# DSO_Clock.net
KiCad netlist of a schematic drawn in Altium Designer
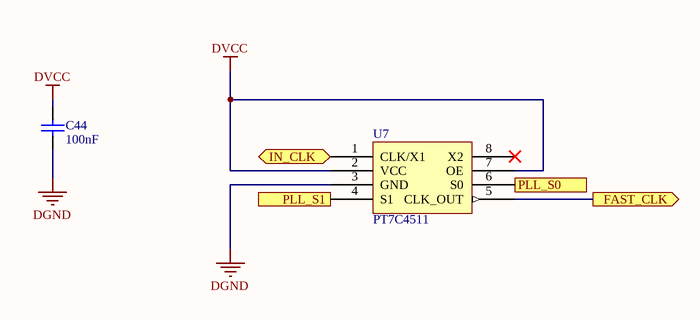
[diagram p0: DSO_Clock.SchDoc]

(export (version "E")
  (design (tool "Eeschema 10.0.6"))
  (components
    (comp (ref "C44")
      (value "100nF")
      (footprint "0805C")
      (description "Capacitor")
      (fields (field (name "REVIEWED BY") "RM - 2018/08/05"))
      (libsource (lib "DSO") (part "C"))
    )
    (comp (ref "U7")
      (value "PT7C4511")
      (footprint "SOIC-8")
      (description "PLL Clock Multiplier")
      (fields (field (name "REVIEWED BY") "RM - 2018/08/05"))
      (libsource (lib "DSO") (part "PT7C4511"))
    )
  )
  (nets
    (net (code "1") (name "/FAST_CLK") (class "Default")
      (node (ref "U7") (pin "5") (pinfunction "CLK_OUT_5") (pintype "output"))
    )
    (net (code "2") (name "/IN_CLK") (class "Default")
      (node (ref "U7") (pin "1") (pinfunction "CLK/X1_1") (pintype "passive"))
    )
    (net (code "3") (name "/PLL_S0") (class "Default")
      (node (ref "U7") (pin "6") (pinfunction "S0_6") (pintype "passive"))
    )
    (net (code "4") (name "/PLL_S1") (class "Default")
      (node (ref "U7") (pin "4") (pinfunction "S1_4") (pintype "passive"))
    )
    (net (code "5") (name "DGND") (class "Default")
      (node (ref "C44") (pin "2") (pinfunction "2_2") (pintype "passive"))
      (node (ref "U7") (pin "3") (pinfunction "GND_3") (pintype "passive"))
    )
    (net (code "6") (name "DVCC") (class "Default")
      (node (ref "C44") (pin "1") (pinfunction "1_1") (pintype "passive"))
      (node (ref "U7") (pin "2") (pinfunction "VCC_2") (pintype "passive"))
      (node (ref "U7") (pin "7") (pinfunction "OE_7") (pintype "passive"))
    )
    (net (code "7") (name "unconnected-(U7-X2-Pad8)") (class "Default")
      (node (ref "U7") (pin "8") (pinfunction "X2_8") (pintype "passive+no_connect"))
    )
  )
)
